# DIY_OpenEVSE_PLUS_30A.net
KiCad netlist of a schematic drawn in EAGLE
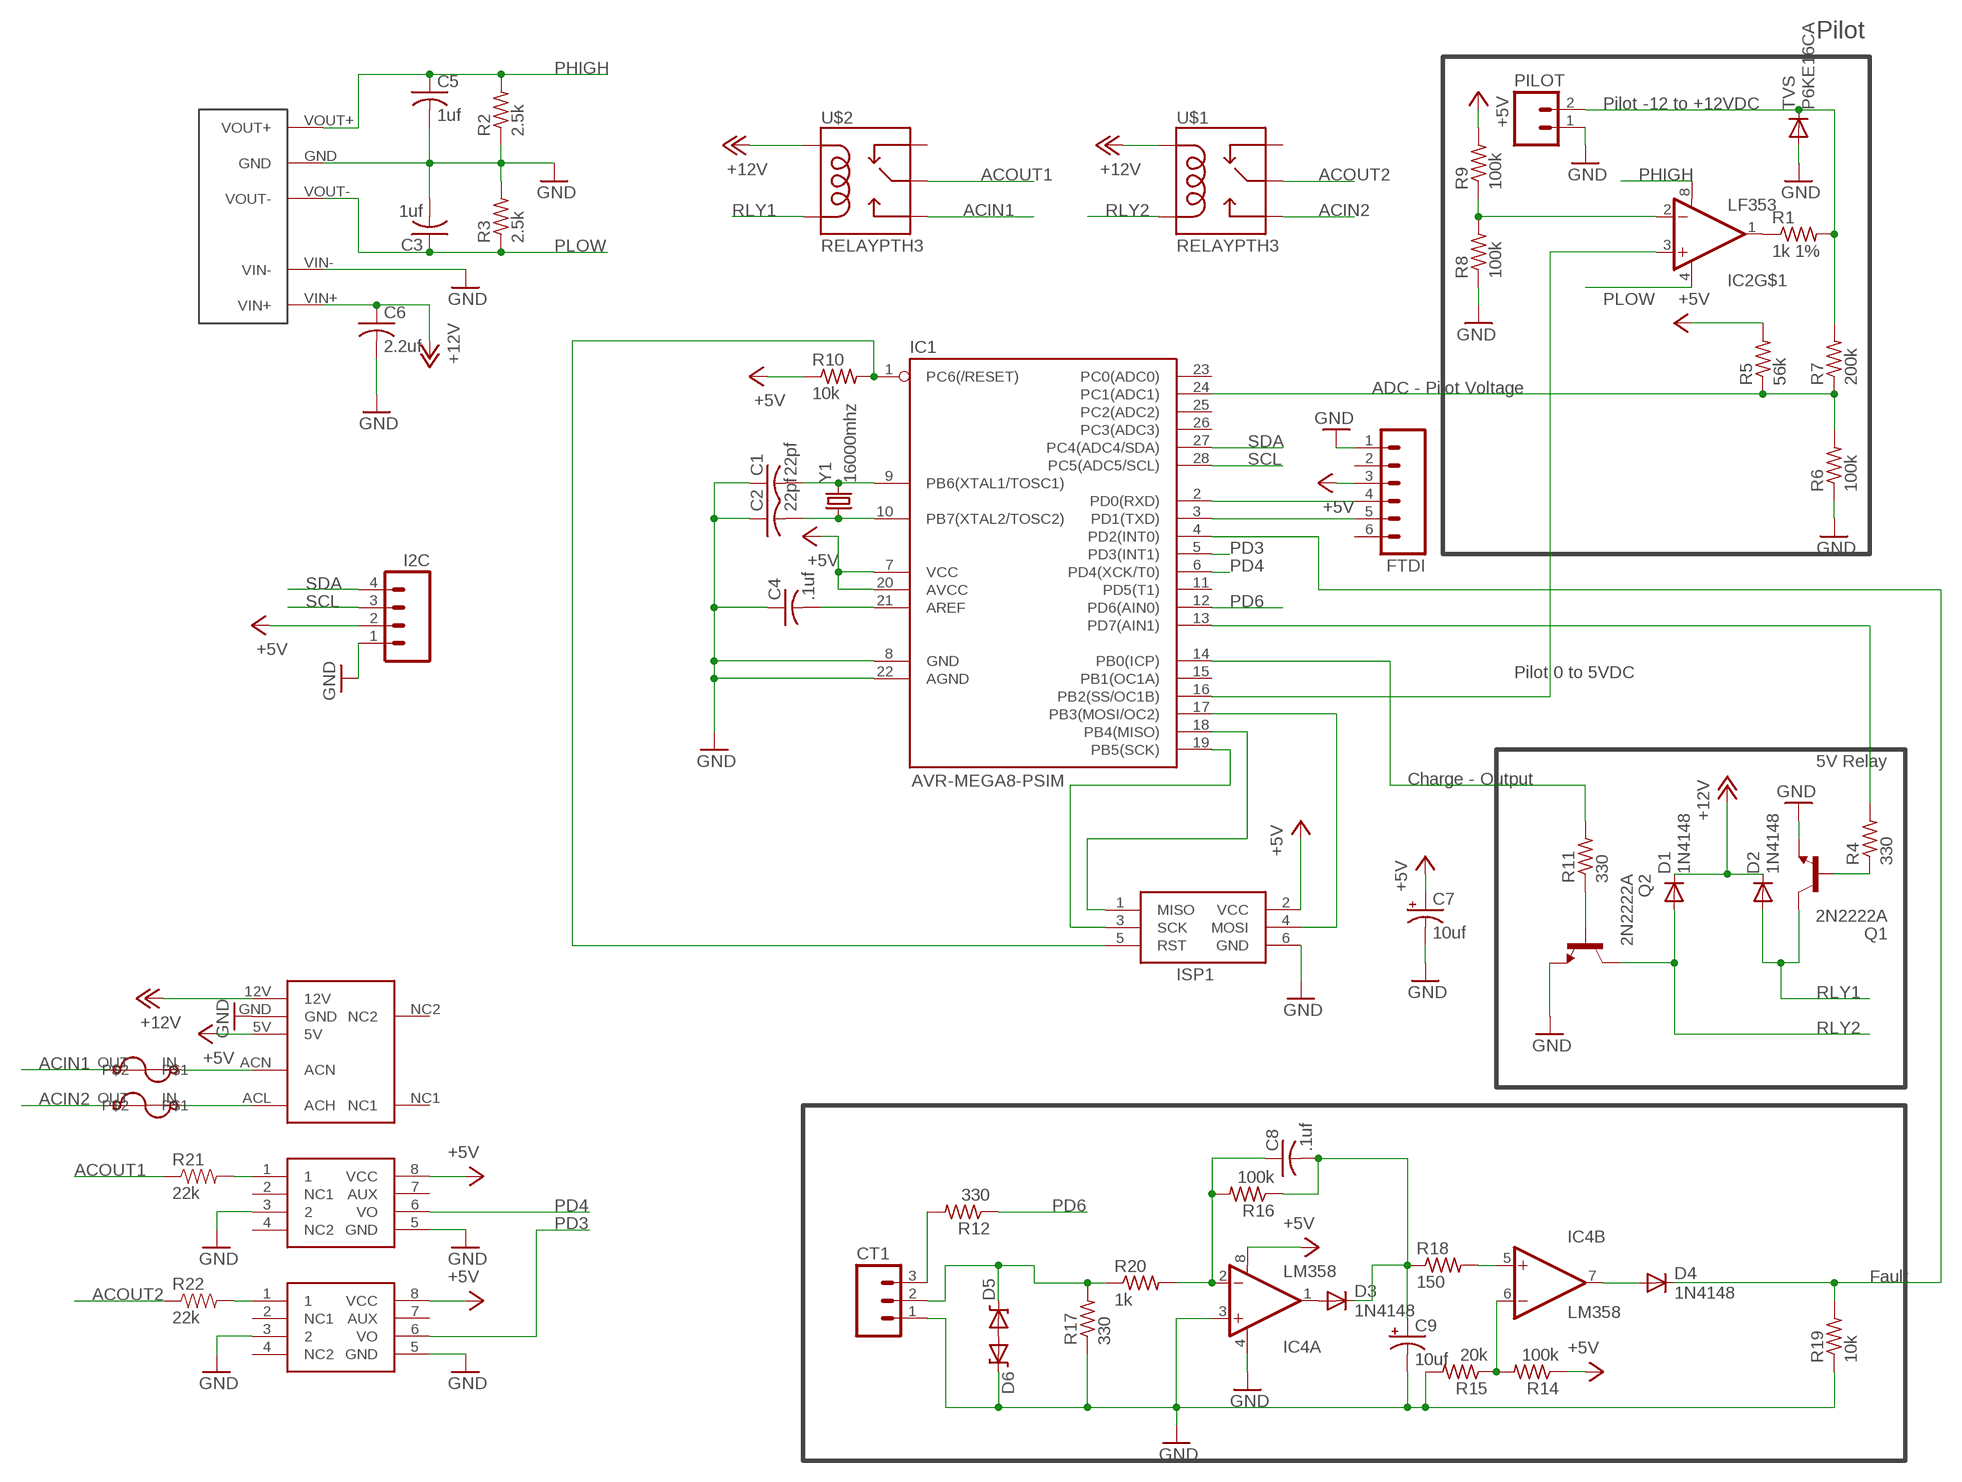
[diagram p0: schematic, sheet 1]

(export (version "E")
  (design (tool "Eeschema 10.0.6"))
  (components
    (comp (ref "C1")
      (value "22pf")
      (footprint "eagle-import:C025-024X044")
      (libsource (lib "eagle-import") (part "C-US025-024X044"))
    )
    (comp (ref "C2")
      (value "22pf")
      (footprint "eagle-import:C025-024X044")
      (libsource (lib "eagle-import") (part "C-US025-024X044"))
    )
    (comp (ref "C3")
      (value "1uf")
      (footprint "eagle-import:C025-024X044")
      (libsource (lib "eagle-import") (part "C-US025-024X044"))
    )
    (comp (ref "C4")
      (value ".1uf")
      (footprint "eagle-import:C025-024X044")
      (libsource (lib "eagle-import") (part "C-US025-024X044"))
    )
    (comp (ref "C5")
      (value "1uf")
      (footprint "eagle-import:C025-024X044")
      (libsource (lib "eagle-import") (part "C-US025-024X044"))
    )
    (comp (ref "C6")
      (value "2.2uf")
      (footprint "eagle-import:C025-024X044")
      (libsource (lib "eagle-import") (part "C-US025-024X044"))
    )
    (comp (ref "C7")
      (value "10uf")
      (footprint "eagle-import:CPOL-RADIAL-10UF-25V")
      (libsource (lib "eagle-import") (part "CAP_POLPTH2"))
    )
    (comp (ref "C8")
      (value ".1uf")
      (footprint "eagle-import:C025-024X044")
      (libsource (lib "eagle-import") (part "C-US025-024X044"))
    )
    (comp (ref "C9")
      (value "10uf")
      (footprint "eagle-import:CPOL-RADIAL-10UF-25V")
      (libsource (lib "eagle-import") (part "CAP_POLPTH2"))
    )
    (comp (ref "CT1")
      (value "M03LOCK")
      (footprint "eagle-import:1X03_LOCK")
      (libsource (lib "eagle-import") (part "M03LOCK"))
    )
    (comp (ref "D1")
      (value "1N4148")
      (footprint "eagle-import:DIODE-1N4148")
      (libsource (lib "eagle-import") (part "DIODE1N4148"))
    )
    (comp (ref "D2")
      (value "1N4148")
      (footprint "eagle-import:DIODE-1N4148")
      (libsource (lib "eagle-import") (part "DIODE1N4148"))
    )
    (comp (ref "D3")
      (value "1N4148")
      (footprint "eagle-import:DIODE-1N4148")
      (libsource (lib "eagle-import") (part "DIODE1N4148"))
    )
    (comp (ref "D4")
      (value "1N4148")
      (footprint "eagle-import:DIODE-1N4148")
      (libsource (lib "eagle-import") (part "DIODE1N4148"))
    )
    (comp (ref "D5")
      (value "DIODE-ZENERPTH")
      (footprint "eagle-import:DIODE-ZENER")
      (libsource (lib "eagle-import") (part "DIODE-ZENERPTH"))
    )
    (comp (ref "D6")
      (value "DIODE-ZENERPTH")
      (footprint "eagle-import:DIODE-ZENER")
      (libsource (lib "eagle-import") (part "DIODE-ZENERPTH"))
    )
    (comp (ref "DCDC")
      (value "D107E")
      (footprint "eagle-import:DCDC_SIP")
      (libsource (lib "eagle-import") (part "DCDC_SIP"))
    )
    (comp (ref "FTDI")
      (value "M06LOCK")
      (footprint "eagle-import:1X06_LOCK")
      (libsource (lib "eagle-import") (part "M06LOCK"))
    )
    (comp (ref "I2C")
      (value "M04LOCK")
      (footprint "eagle-import:1X04_LOCK")
      (libsource (lib "eagle-import") (part "M04LOCK"))
    )
    (comp (ref "IC1")
      (value "AVR-MEGA8-PSIM")
      (footprint "eagle-import:DIL28-3-SIMON")
      (libsource (lib "eagle-import") (part "AVR-MEGA8-PSIM"))
    )
    (comp (ref "IC2")
      (value "LF353")
      (footprint "eagle-import:DIP08")
      (libsource (lib "eagle-import") (part "LM358"))
    )
    (comp (ref "IC3")
      (value "MID400")
      (footprint "eagle-import:DIP08")
      (libsource (lib "eagle-import") (part "MID400"))
    )
    (comp (ref "IC4")
      (value "LM358")
      (footprint "eagle-import:DIP08")
      (libsource (lib "eagle-import") (part "OPAMP-DUALDIP"))
    )
    (comp (ref "IC5")
      (value "MID400")
      (footprint "eagle-import:DIP08")
      (libsource (lib "eagle-import") (part "MID400"))
    )
    (comp (ref "ISP1")
      (value "AVRISP-6")
      (footprint "eagle-import:AVRISP")
      (libsource (lib "eagle-import") (part "AVRISP-6"))
    )
    (comp (ref "PILOT")
      (value "M025MM")
      (footprint "eagle-import:SCREWTERMINAL-5MM-2")
      (libsource (lib "eagle-import") (part "M025MM"))
    )
    (comp (ref "Q1")
      (value "2N2222A")
      (footprint "eagle-import:TO18")
      (libsource (lib "eagle-import") (part "2N2222A"))
    )
    (comp (ref "Q2")
      (value "2N2222A")
      (footprint "eagle-import:TO18")
      (libsource (lib "eagle-import") (part "2N2222A"))
    )
    (comp (ref "R1")
      (value "1k 1%")
      (footprint "eagle-import:0204_7")
      (libsource (lib "eagle-import") (part "R-US_0204/7"))
    )
    (comp (ref "R2")
      (value "2.5k")
      (footprint "eagle-import:0204_7")
      (libsource (lib "eagle-import") (part "R-US_0204/7"))
    )
    (comp (ref "R3")
      (value "2.5k")
      (footprint "eagle-import:0204_7")
      (libsource (lib "eagle-import") (part "R-US_0204/7"))
    )
    (comp (ref "R4")
      (value "330")
      (footprint "eagle-import:0204_7")
      (libsource (lib "eagle-import") (part "R-US_0204/7"))
    )
    (comp (ref "R5")
      (value "56k")
      (footprint "eagle-import:0204_7")
      (libsource (lib "eagle-import") (part "R-US_0204/7"))
    )
    (comp (ref "R6")
      (value "100k")
      (footprint "eagle-import:0204_7")
      (libsource (lib "eagle-import") (part "R-US_0204/7"))
    )
    (comp (ref "R7")
      (value "200k")
      (footprint "eagle-import:0204_7")
      (libsource (lib "eagle-import") (part "R-US_0204/7"))
    )
    (comp (ref "R8")
      (value "100k")
      (footprint "eagle-import:0204_7")
      (libsource (lib "eagle-import") (part "R-US_0204/7"))
    )
    (comp (ref "R9")
      (value "100k")
      (footprint "eagle-import:0204_7")
      (libsource (lib "eagle-import") (part "R-US_0204/7"))
    )
    (comp (ref "R10")
      (value "10k")
      (footprint "eagle-import:0204_7")
      (libsource (lib "eagle-import") (part "R-US_0204/7"))
    )
    (comp (ref "R11")
      (value "330")
      (footprint "eagle-import:0204_7")
      (libsource (lib "eagle-import") (part "R-US_0204/7"))
    )
    (comp (ref "R12")
      (value "330")
      (footprint "eagle-import:0204_7")
      (libsource (lib "eagle-import") (part "R-US_0204/7"))
    )
    (comp (ref "R14")
      (value "100k")
      (footprint "eagle-import:0204_7")
      (libsource (lib "eagle-import") (part "R-US_0204/7"))
    )
    (comp (ref "R15")
      (value "20k")
      (footprint "eagle-import:0204_7")
      (libsource (lib "eagle-import") (part "R-US_0204/7"))
    )
    (comp (ref "R16")
      (value "100k")
      (footprint "eagle-import:0204_7")
      (libsource (lib "eagle-import") (part "R-US_0204/7"))
    )
    (comp (ref "R17")
      (value "330")
      (footprint "eagle-import:0204_7")
      (libsource (lib "eagle-import") (part "R-US_0204/7"))
    )
    (comp (ref "R18")
      (value "150")
      (footprint "eagle-import:0204_7")
      (libsource (lib "eagle-import") (part "R-US_0204/7"))
    )
    (comp (ref "R19")
      (value "10k")
      (footprint "eagle-import:0204_7")
      (libsource (lib "eagle-import") (part "R-US_0204/7"))
    )
    (comp (ref "R20")
      (value "1k")
      (footprint "eagle-import:0204_7")
      (libsource (lib "eagle-import") (part "R-US_0204/7"))
    )
    (comp (ref "R21")
      (value "22k")
      (footprint "eagle-import:AXIAL-0.4")
      (libsource (lib "eagle-import") (part "RESISTORPTH-1/4W"))
    )
    (comp (ref "R22")
      (value "22k")
      (footprint "eagle-import:AXIAL-0.4")
      (libsource (lib "eagle-import") (part "RESISTORPTH-1/4W"))
    )
    (comp (ref "TVS")
      (value "P6KE16CA")
      (footprint "eagle-import:DIODE-1N4001")
      (libsource (lib "eagle-import") (part "DIODEPTH"))
    )
    (comp (ref "U$1")
      (value "RELAYPTH3")
      (footprint "eagle-import:RELAY-T9A-2")
      (libsource (lib "eagle-import") (part "RELAYPTH3"))
    )
    (comp (ref "U$2")
      (value "RELAYPTH3")
      (footprint "eagle-import:RELAY-T9A-2")
      (libsource (lib "eagle-import") (part "RELAYPTH3"))
    )
    (comp (ref "U$3")
      (value "BEL1AFUSE")
      (footprint "eagle-import:BELFUSE1A")
      (libsource (lib "eagle-import") (part "BEL1AFUSE"))
    )
    (comp (ref "U$4")
      (value "MPM-04E-1205")
      (footprint "eagle-import:MPM-04E-1205")
      (libsource (lib "eagle-import") (part "MPM-04E-1205"))
    )
    (comp (ref "U$5")
      (value "BEL1AFUSE")
      (footprint "eagle-import:BELFUSE1A")
      (libsource (lib "eagle-import") (part "BEL1AFUSE"))
    )
    (comp (ref "Y1")
      (value "16000mhz")
      (footprint "eagle-import:HC49U-V")
      (libsource (lib "eagle-import") (part "CRYSTALHC49UV"))
    )
  )
  (nets
    (net (code "1") (name "+5V") (class "Default")
      (node (ref "C7") (pin "1") (pinfunction "+_1") (pintype "passive"))
      (node (ref "FTDI") (pin "3") (pinfunction "3_3") (pintype "passive"))
      (node (ref "I2C") (pin "2") (pinfunction "2_2") (pintype "passive"))
      (node (ref "IC1") (pin "20") (pinfunction "AVCC_20") (pintype "bidirectional"))
      (node (ref "IC1") (pin "7") (pinfunction "VCC_7") (pintype "bidirectional"))
      (node (ref "IC3") (pin "8") (pinfunction "VCC_8") (pintype "bidirectional"))
      (node (ref "IC4") (pin "8") (pinfunction "V+_8") (pintype "power_in"))
      (node (ref "IC5") (pin "8") (pinfunction "VCC_8") (pintype "bidirectional"))
      (node (ref "ISP1") (pin "2") (pinfunction "VCC_2") (pintype "power_in"))
      (node (ref "R10") (pin "1") (pinfunction "1_1") (pintype "passive"))
      (node (ref "R14") (pin "1") (pinfunction "1_1") (pintype "passive"))
      (node (ref "R5") (pin "2") (pinfunction "2_2") (pintype "passive"))
      (node (ref "R9") (pin "2") (pinfunction "2_2") (pintype "passive"))
      (node (ref "U$4") (pin "5V") (pinfunction "5V_5V") (pintype "bidirectional"))
    )
    (net (code "2") (name "+12V") (class "Default")
      (node (ref "C6") (pin "1") (pinfunction "1_1") (pintype "passive"))
      (node (ref "D1") (pin "C") (pinfunction "C_C") (pintype "passive"))
      (node (ref "D2") (pin "C") (pinfunction "C_C") (pintype "passive"))
      (node (ref "DCDC") (pin "VIN+") (pinfunction "VIN+_VIN+") (pintype "bidirectional"))
      (node (ref "U$1") (pin "COIL1") (pinfunction "COIL1_COIL1") (pintype "bidirectional"))
      (node (ref "U$2") (pin "COIL1") (pinfunction "COIL1_COIL1") (pintype "bidirectional"))
      (node (ref "U$4") (pin "12V") (pinfunction "12V_12V") (pintype "bidirectional"))
    )
    (net (code "3") (name "/ACIN1") (class "Default")
      (node (ref "U$2") (pin "NO") (pinfunction "NO_NO") (pintype "bidirectional"))
      (node (ref "U$5") (pin "OUT") (pinfunction "P$1_OUT") (pintype "bidirectional"))
    )
    (net (code "4") (name "/ACIN2") (class "Default")
      (node (ref "U$1") (pin "NO") (pinfunction "NO_NO") (pintype "bidirectional"))
      (node (ref "U$3") (pin "OUT") (pinfunction "P$1_OUT") (pintype "bidirectional"))
    )
    (net (code "5") (name "/ACOUT1") (class "Default")
      (node (ref "R21") (pin "P$1") (pinfunction "1_P$1") (pintype "passive"))
      (node (ref "U$2") (pin "MAIN") (pinfunction "MAIN_MAIN") (pintype "bidirectional"))
    )
    (net (code "6") (name "/ACOUT2") (class "Default")
      (node (ref "R22") (pin "P$1") (pinfunction "1_P$1") (pintype "passive"))
      (node (ref "U$1") (pin "MAIN") (pinfunction "MAIN_MAIN") (pintype "bidirectional"))
    )
    (net (code "7") (name "/PD3") (class "Default")
      (node (ref "IC1") (pin "5") (pinfunction "PD3(INT1)_5") (pintype "bidirectional"))
      (node (ref "IC5") (pin "6") (pinfunction "VO_6") (pintype "bidirectional"))
    )
    (net (code "8") (name "/PD4") (class "Default")
      (node (ref "IC1") (pin "6") (pinfunction "PD4(XCK/T0)_6") (pintype "bidirectional"))
      (node (ref "IC3") (pin "6") (pinfunction "VO_6") (pintype "bidirectional"))
    )
    (net (code "9") (name "/PD6") (class "Default")
      (node (ref "IC1") (pin "12") (pinfunction "PD6(AIN0)_12") (pintype "bidirectional"))
      (node (ref "R12") (pin "1") (pinfunction "1_1") (pintype "passive"))
    )
    (net (code "10") (name "/PHIGH") (class "Default")
      (node (ref "C5") (pin "1") (pinfunction "1_1") (pintype "passive"))
      (node (ref "DCDC") (pin "VOUT+") (pinfunction "VOUT+_VOUT+") (pintype "bidirectional"))
      (node (ref "IC2") (pin "8") (pinfunction "V+_8") (pintype "power_in"))
      (node (ref "R2") (pin "2") (pinfunction "2_2") (pintype "passive"))
    )
    (net (code "11") (name "/PLOW") (class "Default")
      (node (ref "C3") (pin "1") (pinfunction "1_1") (pintype "passive"))
      (node (ref "DCDC") (pin "VOUT-") (pinfunction "VOUT-_VOUT-") (pintype "bidirectional"))
      (node (ref "IC2") (pin "4") (pinfunction "V-_4") (pintype "power_in"))
      (node (ref "R3") (pin "1") (pinfunction "1_1") (pintype "passive"))
    )
    (net (code "12") (name "/RLY1") (class "Default")
      (node (ref "D2") (pin "A") (pinfunction "A_A") (pintype "passive"))
      (node (ref "Q1") (pin "3") (pinfunction "C_3") (pintype "passive"))
      (node (ref "U$2") (pin "COIL2") (pinfunction "COIL2_COIL2") (pintype "bidirectional"))
    )
    (net (code "13") (name "/RLY2") (class "Default")
      (node (ref "D1") (pin "A") (pinfunction "A_A") (pintype "passive"))
      (node (ref "Q2") (pin "3") (pinfunction "C_3") (pintype "passive"))
      (node (ref "U$1") (pin "COIL2") (pinfunction "COIL2_COIL2") (pintype "bidirectional"))
    )
    (net (code "14") (name "/SCL") (class "Default")
      (node (ref "I2C") (pin "3") (pinfunction "3_3") (pintype "passive"))
      (node (ref "IC1") (pin "28") (pinfunction "PC5(ADC5/SCL)_28") (pintype "bidirectional"))
    )
    (net (code "15") (name "/SDA") (class "Default")
      (node (ref "I2C") (pin "4") (pinfunction "4_4") (pintype "passive"))
      (node (ref "IC1") (pin "27") (pinfunction "PC4(ADC4/SDA)_27") (pintype "bidirectional"))
    )
    (net (code "16") (name "GND") (class "Default")
      (node (ref "C1") (pin "1") (pinfunction "1_1") (pintype "passive"))
      (node (ref "C2") (pin "1") (pinfunction "1_1") (pintype "passive"))
      (node (ref "C3") (pin "2") (pinfunction "2_2") (pintype "passive"))
      (node (ref "C4") (pin "1") (pinfunction "1_1") (pintype "passive"))
      (node (ref "C5") (pin "2") (pinfunction "2_2") (pintype "passive"))
      (node (ref "C6") (pin "2") (pinfunction "2_2") (pintype "passive"))
      (node (ref "C7") (pin "2") (pinfunction "-_2") (pintype "passive"))
      (node (ref "C9") (pin "2") (pinfunction "-_2") (pintype "passive"))
      (node (ref "CT1") (pin "1") (pinfunction "1_1") (pintype "passive"))
      (node (ref "D6") (pin "P$1") (pinfunction "C_P$1") (pintype "passive"))
      (node (ref "DCDC") (pin "GND") (pinfunction "GND_GND") (pintype "bidirectional"))
      (node (ref "DCDC") (pin "VIN-") (pinfunction "VIN-_VIN-") (pintype "bidirectional"))
      (node (ref "FTDI") (pin "1") (pinfunction "1_1") (pintype "passive"))
      (node (ref "I2C") (pin "1") (pinfunction "1_1") (pintype "passive"))
      (node (ref "IC1") (pin "22") (pinfunction "AGND_22") (pintype "bidirectional"))
      (node (ref "IC1") (pin "8") (pinfunction "GND_8") (pintype "bidirectional"))
      (node (ref "IC3") (pin "3") (pinfunction "2_3") (pintype "bidirectional"))
      (node (ref "IC3") (pin "5") (pinfunction "GND_5") (pintype "bidirectional"))
      (node (ref "IC4") (pin "3") (pinfunction "+IN_3") (pintype "input"))
      (node (ref "IC4") (pin "4") (pinfunction "V-_4") (pintype "power_in"))
      (node (ref "IC5") (pin "3") (pinfunction "2_3") (pintype "bidirectional"))
      (node (ref "IC5") (pin "5") (pinfunction "GND_5") (pintype "bidirectional"))
      (node (ref "ISP1") (pin "6") (pinfunction "GND_6") (pintype "power_in"))
      (node (ref "PILOT") (pin "1") (pinfunction "1_1") (pintype "passive"))
      (node (ref "Q1") (pin "1") (pinfunction "E_1") (pintype "passive"))
      (node (ref "Q2") (pin "1") (pinfunction "E_1") (pintype "passive"))
      (node (ref "R15") (pin "2") (pinfunction "2_2") (pintype "passive"))
      (node (ref "R17") (pin "1") (pinfunction "1_1") (pintype "passive"))
      (node (ref "R19") (pin "1") (pinfunction "1_1") (pintype "passive"))
      (node (ref "R2") (pin "1") (pinfunction "1_1") (pintype "passive"))
      (node (ref "R3") (pin "2") (pinfunction "2_2") (pintype "passive"))
      (node (ref "R6") (pin "1") (pinfunction "1_1") (pintype "passive"))
      (node (ref "R8") (pin "1") (pinfunction "1_1") (pintype "passive"))
      (node (ref "TVS") (pin "A") (pinfunction "A_A") (pintype "passive"))
      (node (ref "U$4") (pin "GND") (pinfunction "GND_GND") (pintype "bidirectional"))
    )
    (net (code "17") (name "Net-(C9-+)") (class "Default")
      (node (ref "C8") (pin "2") (pinfunction "2_2") (pintype "passive"))
      (node (ref "C9") (pin "1") (pinfunction "+_1") (pintype "passive"))
      (node (ref "D3") (pin "C") (pinfunction "C_C") (pintype "passive"))
      (node (ref "R16") (pin "1") (pinfunction "1_1") (pintype "passive"))
      (node (ref "R18") (pin "1") (pinfunction "1_1") (pintype "passive"))
    )
    (net (code "18") (name "Net-(CT1-Pad3)") (class "Default")
      (node (ref "CT1") (pin "3") (pinfunction "3_3") (pintype "passive"))
      (node (ref "R12") (pin "2") (pinfunction "2_2") (pintype "passive"))
    )
    (net (code "19") (name "Net-(D5-A)") (class "Default")
      (node (ref "D5") (pin "P$2") (pinfunction "A_P$2") (pintype "passive"))
      (node (ref "D6") (pin "P$2") (pinfunction "A_P$2") (pintype "passive"))
    )
    (net (code "20") (name "Net-(D5-C)") (class "Default")
      (node (ref "CT1") (pin "2") (pinfunction "2_2") (pintype "passive"))
      (node (ref "D5") (pin "P$1") (pinfunction "C_P$1") (pintype "passive"))
      (node (ref "R17") (pin "2") (pinfunction "2_2") (pintype "passive"))
      (node (ref "R20") (pin "1") (pinfunction "1_1") (pintype "passive"))
    )
    (net (code "21") (name "Net-(IC1-AREF)") (class "Default")
      (node (ref "C4") (pin "2") (pinfunction "2_2") (pintype "passive"))
      (node (ref "IC1") (pin "21") (pinfunction "AREF_21") (pintype "bidirectional"))
    )
    (net (code "22") (name "Net-(IC1-PB0(ICP))") (class "Default")
      (node (ref "IC1") (pin "14") (pinfunction "PB0(ICP)_14") (pintype "bidirectional"))
      (node (ref "R11") (pin "2") (pinfunction "2_2") (pintype "passive"))
    )
    (net (code "23") (name "Net-(IC1-PB2(SS{slash}OC1B))") (class "Default")
      (node (ref "IC1") (pin "16") (pinfunction "PB2(SS/OC1B)_16") (pintype "bidirectional"))
      (node (ref "IC2") (pin "3") (pinfunction "+IN_3") (pintype "input"))
    )
    (net (code "24") (name "Net-(IC1-PB3(MOSI{slash}OC2))") (class "Default")
      (node (ref "IC1") (pin "17") (pinfunction "PB3(MOSI/OC2)_17") (pintype "bidirectional"))
      (node (ref "ISP1") (pin "4") (pinfunction "MOSI_4") (pintype "output"))
    )
    (net (code "25") (name "Net-(IC1-PB4(MISO))") (class "Default")
      (node (ref "IC1") (pin "18") (pinfunction "PB4(MISO)_18") (pintype "bidirectional"))
      (node (ref "ISP1") (pin "1") (pinfunction "MISO_1") (pintype "input"))
    )
    (net (code "26") (name "Net-(IC1-PB5(SCK))") (class "Default")
      (node (ref "IC1") (pin "19") (pinfunction "PB5(SCK)_19") (pintype "bidirectional"))
      (node (ref "ISP1") (pin "3") (pinfunction "SCK_3") (pintype "output"))
    )
    (net (code "27") (name "Net-(IC1-PB6(XTAL1{slash}TOSC1))") (class "Default")
      (node (ref "C1") (pin "2") (pinfunction "2_2") (pintype "passive"))
      (node (ref "IC1") (pin "9") (pinfunction "PB6(XTAL1/TOSC1)_9") (pintype "bidirectional"))
      (node (ref "Y1") (pin "2") (pinfunction "2_2") (pintype "passive"))
    )
    (net (code "28") (name "Net-(IC1-PB7(XTAL2{slash}TOSC2))") (class "Default")
      (node (ref "C2") (pin "2") (pinfunction "2_2") (pintype "passive"))
      (node (ref "IC1") (pin "10") (pinfunction "PB7(XTAL2/TOSC2)_10") (pintype "bidirectional"))
      (node (ref "Y1") (pin "1") (pinfunction "1_1") (pintype "passive"))
    )
    (net (code "29") (name "Net-(IC1-PC1(ADC1))") (class "Default")
      (node (ref "IC1") (pin "24") (pinfunction "PC1(ADC1)_24") (pintype "bidirectional"))
      (node (ref "R5") (pin "1") (pinfunction "1_1") (pintype "passive"))
      (node (ref "R6") (pin "2") (pinfunction "2_2") (pintype "passive"))
      (node (ref "R7") (pin "1") (pinfunction "1_1") (pintype "passive"))
    )
    (net (code "30") (name "Net-(IC1-PC6({slash}RESET))") (class "Default")
      (node (ref "IC1") (pin "1") (pinfunction "PC6(/RESET)_1") (pintype "bidirectional"))
      (node (ref "ISP1") (pin "5") (pinfunction "RST_5") (pintype "output"))
      (node (ref "R10") (pin "2") (pinfunction "2_2") (pintype "passive"))
    )
    (net (code "31") (name "Net-(IC1-PD0(RXD))") (class "Default")
      (node (ref "FTDI") (pin "4") (pinfunction "4_4") (pintype "passive"))
      (node (ref "IC1") (pin "2") (pinfunction "PD0(RXD)_2") (pintype "bidirectional"))
    )
    (net (code "32") (name "Net-(IC1-PD1(TXD))") (class "Default")
      (node (ref "FTDI") (pin "5") (pinfunction "5_5") (pintype "passive"))
      (node (ref "IC1") (pin "3") (pinfunction "PD1(TXD)_3") (pintype "bidirectional"))
    )
    (net (code "33") (name "Net-(IC1-PD2(INT0))") (class "Default")
      (node (ref "D4") (pin "C") (pinfunction "C_C") (pintype "passive"))
      (node (ref "IC1") (pin "4") (pinfunction "PD2(INT0)_4") (pintype "bidirectional"))
      (node (ref "R19") (pin "2") (pinfunction "2_2") (pintype "passive"))
    )
    (net (code "34") (name "Net-(IC1-PD7(AIN1))") (class "Default")
      (node (ref "IC1") (pin "13") (pinfunction "PD7(AIN1)_13") (pintype "bidirectional"))
      (node (ref "R4") (pin "2") (pinfunction "2_2") (pintype "passive"))
    )
    (net (code "35") (name "Net-(IC2A--IN)") (class "Default")
      (node (ref "IC2") (pin "2") (pinfunction "-IN_2") (pintype "input"))
      (node (ref "R8") (pin "2") (pinfunction "2_2") (pintype "passive"))
      (node (ref "R9") (pin "1") (pinfunction "1_1") (pintype "passive"))
    )
    (net (code "36") (name "Net-(IC2A-OUT)") (class "Default")
      (node (ref "IC2") (pin "1") (pinfunction "OUT_1") (pintype "output"))
      (node (ref "R1") (pin "1") (pinfunction "1_1") (pintype "passive"))
    )
    (net (code "37") (name "Net-(IC4A--IN)") (class "Default")
      (node (ref "C8") (pin "1") (pinfunction "1_1") (pintype "passive"))
      (node (ref "IC4") (pin "2") (pinfunction "-IN_2") (pintype "input"))
      (node (ref "R16") (pin "2") (pinfunction "2_2") (pintype "passive"))
      (node (ref "R20") (pin "2") (pinfunction "2_2") (pintype "passive"))
    )
    (net (code "38") (name "Net-(IC4A-OUT)") (class "Default")
      (node (ref "D3") (pin "A") (pinfunction "A_A") (pintype "passive"))
      (node (ref "IC4") (pin "1") (pinfunction "OUT_1") (pintype "output"))
    )
    (net (code "39") (name "Net-(IC4B-+IN)") (class "Default")
      (node (ref "IC4") (pin "5") (pinfunction "+IN_5") (pintype "input"))
      (node (ref "R18") (pin "2") (pinfunction "2_2") (pintype "passive"))
    )
    (net (code "40") (name "Net-(IC4B--IN)") (class "Default")
      (node (ref "IC4") (pin "6") (pinfunction "-IN_6") (pintype "input"))
      (node (ref "R14") (pin "2") (pinfunction "2_2") (pintype "passive"))
      (node (ref "R15") (pin "1") (pinfunction "1_1") (pintype "passive"))
    )
    (net (code "41") (name "Net-(IC4B-OUT)") (class "Default")
      (node (ref "D4") (pin "A") (pinfunction "A_A") (pintype "passive"))
      (node (ref "IC4") (pin "7") (pinfunction "OUT_7") (pintype "output"))
    )
    (net (code "42") (name "Net-(PILOT-Pad2)") (class "Default")
      (node (ref "PILOT") (pin "2") (pinfunction "2_2") (pintype "passive"))
      (node (ref "R1") (pin "2") (pinfunction "2_2") (pintype "passive"))
      (node (ref "R7") (pin "2") (pinfunction "2_2") (pintype "passive"))
      (node (ref "TVS") (pin "C") (pinfunction "C_C") (pintype "passive"))
    )
    (net (code "43") (name "Net-(Q1-B)") (class "Default")
      (node (ref "Q1") (pin "2") (pinfunction "B_2") (pintype "passive"))
      (node (ref "R4") (pin "1") (pinfunction "1_1") (pintype "passive"))
    )
    (net (code "44") (name "Net-(Q2-B)") (class "Default")
      (node (ref "Q2") (pin "2") (pinfunction "B_2") (pintype "passive"))
      (node (ref "R11") (pin "1") (pinfunction "1_1") (pintype "passive"))
    )
    (net (code "45") (name "Net-(R21-2)") (class "Default")
      (node (ref "IC3") (pin "1") (pinfunction "1_1") (pintype "bidirectional"))
      (node (ref "R21") (pin "P$2") (pinfunction "2_P$2") (pintype "passive"))
    )
    (net (code "46") (name "Net-(R22-2)") (class "Default")
      (node (ref "IC5") (pin "1") (pinfunction "1_1") (pintype "bidirectional"))
      (node (ref "R22") (pin "P$2") (pinfunction "2_P$2") (pintype "passive"))
    )
    (net (code "47") (name "Net-(U$3-P$2)") (class "Default")
      (node (ref "U$3") (pin "IN") (pinfunction "P$2_IN") (pintype "bidirectional"))
      (node (ref "U$4") (pin "ACL") (pinfunction "ACH_ACL") (pintype "bidirectional"))
    )
    (net (code "48") (name "Net-(U$5-P$2)") (class "Default")
      (node (ref "U$4") (pin "ACN") (pinfunction "ACN_ACN") (pintype "bidirectional"))
      (node (ref "U$5") (pin "IN") (pinfunction "P$2_IN") (pintype "bidirectional"))
    )
    (net (code "49") (name "unconnected-(FTDI-Pad2)") (class "Default")
      (node (ref "FTDI") (pin "2") (pinfunction "2_2") (pintype "passive"))
    )
    (net (code "50") (name "unconnected-(FTDI-Pad6)") (class "Default")
      (node (ref "FTDI") (pin "6") (pinfunction "6_6") (pintype "passive"))
    )
    (net (code "51") (name "unconnected-(IC1-PB1(OC1A)-Pad15)") (class "Default")
      (node (ref "IC1") (pin "15") (pinfunction "PB1(OC1A)_15") (pintype "bidirectional"))
    )
    (net (code "52") (name "unconnected-(IC1-PC0(ADC0)-Pad23)") (class "Default")
      (node (ref "IC1") (pin "23") (pinfunction "PC0(ADC0)_23") (pintype "bidirectional"))
    )
    (net (code "53") (name "unconnected-(IC1-PC2(ADC2)-Pad25)") (class "Default")
      (node (ref "IC1") (pin "25") (pinfunction "PC2(ADC2)_25") (pintype "bidirectional"))
    )
    (net (code "54") (name "unconnected-(IC1-PC3(ADC3)-Pad26)") (class "Default")
      (node (ref "IC1") (pin "26") (pinfunction "PC3(ADC3)_26") (pintype "bidirectional"))
    )
    (net (code "55") (name "unconnected-(IC1-PD5(T1)-Pad11)") (class "Default")
      (node (ref "IC1") (pin "11") (pinfunction "PD5(T1)_11") (pintype "bidirectional"))
    )
    (net (code "56") (name "unconnected-(IC3-AUX-Pad7)") (class "Default")
      (node (ref "IC3") (pin "7") (pinfunction "AUX_7") (pintype "bidirectional"))
    )
    (net (code "57") (name "unconnected-(IC3-NC1-Pad2)") (class "Default")
      (node (ref "IC3") (pin "2") (pinfunction "NC1_2") (pintype "bidirectional"))
    )
    (net (code "58") (name "unconnected-(IC3-NC2-Pad4)") (class "Default")
      (node (ref "IC3") (pin "4") (pinfunction "NC2_4") (pintype "bidirectional"))
    )
    (net (code "59") (name "unconnected-(IC5-AUX-Pad7)") (class "Default")
      (node (ref "IC5") (pin "7") (pinfunction "AUX_7") (pintype "bidirectional"))
    )
    (net (code "60") (name "unconnected-(IC5-NC1-Pad2)") (class "Default")
      (node (ref "IC5") (pin "2") (pinfunction "NC1_2") (pintype "bidirectional"))
    )
    (net (code "61") (name "unconnected-(IC5-NC2-Pad4)") (class "Default")
      (node (ref "IC5") (pin "4") (pinfunction "NC2_4") (pintype "bidirectional"))
    )
    (net (code "62") (name "unconnected-(U$1-PadNC)") (class "Default")
      (node (ref "U$1") (pin "NC") (pinfunction "NC_NC") (pintype "bidirectional"))
    )
    (net (code "63") (name "unconnected-(U$2-PadNC)") (class "Default")
      (node (ref "U$2") (pin "NC") (pinfunction "NC_NC") (pintype "bidirectional"))
    )
    (net (code "64") (name "unconnected-(U$4-PadNC1)") (class "Default")
      (node (ref "U$4") (pin "NC1") (pinfunction "NC1_NC1") (pintype "bidirectional"))
    )
    (net (code "65") (name "unconnected-(U$4-PadNC2)") (class "Default")
      (node (ref "U$4") (pin "NC2") (pinfunction "NC2_NC2") (pintype "bidirectional"))
    )
  )
)
